# DriverPrototype.net
KiCad netlist of a schematic drawn in Altium Designer
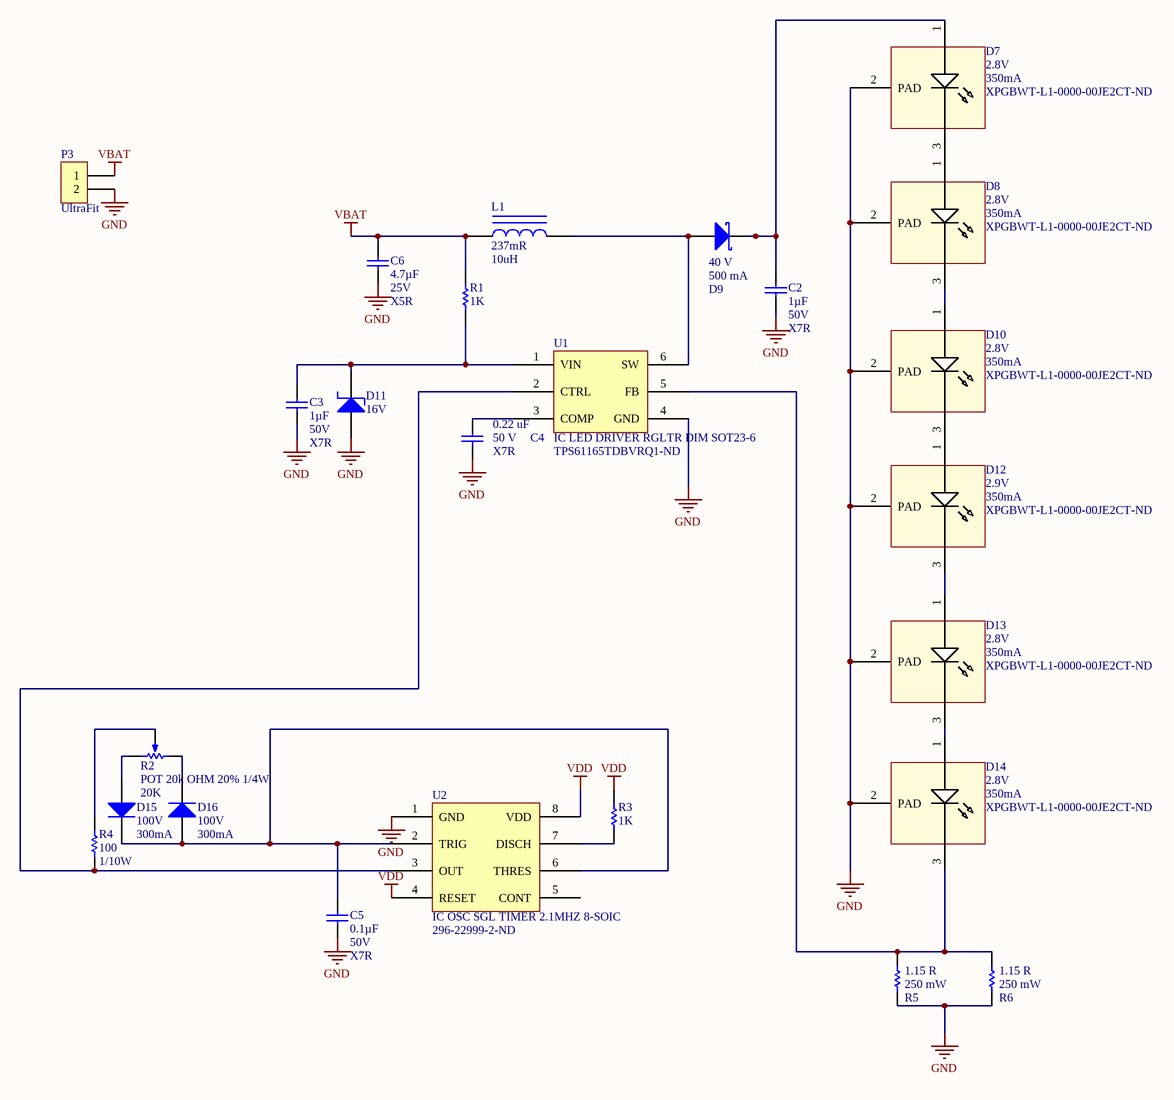
[diagram p0: DriverPrototype.SchDoc]

(export (version "E")
  (design (tool "Eeschema 10.0.6"))
  (components
    (comp (ref "C2")
      (value "CAP CER 1UF 50V 10% X7R 0603")
      (footprint "CAP, 0603")
      (description "1µF ±10% 50V Ceramic Capacitor X7R 0603 (1608 Metric)")
      (fields
        (field (name "TOLERANCE") "±10%")
        (field (name "CAPACITANCE") "1µF")
        (field (name "VOLTAGE") "50V")
        (field (name "TEMPERATURE COEFFICIENT") "X7R")
      )
      (libsource (lib "Schematic Diagrams") (part "CAP CER 1UF 50V 10% X7R 0603"))
    )
    (comp (ref "C3")
      (value "CAP CER 1UF 50V 10% X7R 0603")
      (footprint "CAP, 0603")
      (description "1µF ±10% 50V Ceramic Capacitor X7R 0603 (1608 Metric)")
      (fields
        (field (name "TOLERANCE") "±10%")
        (field (name "CAPACITANCE") "1µF")
        (field (name "VOLTAGE") "50V")
        (field (name "TEMPERATURE COEFFICIENT") "X7R")
      )
      (libsource (lib "Schematic Diagrams") (part "CAP CER 1UF 50V 10% X7R 0603"))
    )
    (comp (ref "C4")
      (value "CAP CER 0.22UF 50V X7R 0805")
      (footprint "CAP, 0805")
      (fields
        (field (name "MANUFACTURER") "Samsung")
        (field (name "MANUFACTURER PART NUMBER") "CL21B224KBFNNNE")
        (field (name "TOLERANCE") "10%")
      )
      (libsource (lib "Schematic Diagrams") (part "CAP CER 0.22UF 50V X7R 0805"))
    )
    (comp (ref "C5")
      (value "CAP CER 0.1UF 50V 10% X7R 0603")
      (footprint "CAP, 0603")
      (description "0.10µF ±10% 50V Ceramic Capacitor X7R 0603 (1608 Metric)")
      (fields
        (field (name "TOLERANCE") "±10%")
        (field (name "CAPACITANCE") "0.1µF")
        (field (name "VOLTAGE") "50V")
        (field (name "TEMPERATURE COEFFICIENT") "X7R")
      )
      (libsource (lib "Schematic Diagrams") (part "CAP CER 0.1UF 50V 10% X7R 0603"))
    )
    (comp (ref "C6")
      (value "CAP CER 4700PF 400VAC Y5V RADIAL")
      (footprint "CAP 4700PF 400VAC Y5V RADIAL")
      (description "4.7µF ±10% 25V Ceramic Capacitor X5R 0603 (1608 Metric)")
      (fields
        (field (name "TOLERANCE") "±10%")
        (field (name "CAPACITANCE") "4.7µF")
        (field (name "VOLTAGE") "25V")
        (field (name "TEMPERATURE COEFFICIENT") "X5R")
      )
      (libsource (lib "Schematic Diagrams") (part "CAP CER 4.7UF 25V 10% X5R 0603"))
    )
    (comp (ref "D7")
      (value "LED XLAMP COOL WHITE 5700K 2SMD")
      (footprint "LED CREE XP-E2 1414 2-SMD")
      (description "LED Lighting XLamp® XP-E2 White, Cool 5700K 2.9V 350mA 110° 1414 (3535 Metric)")
      (fields
        (field (name "MANUFACTURER") "Cree")
        (field (name "MANUFACTURER PART NUMBER") "XPGBWT-L1-0000-00JE2")
        (field (name "FORWARD VOLTAGE") "2.8V")
        (field (name "TEST CURRENT") "350mA")
        (field (name "SUPPLIER PART NUMBER 1") "XPGBWT-L1-0000-00JE2CT-ND")
      )
      (libsource (lib "Schematic Diagrams") (part "LED XLAMP COOL WHITE 5700K 2SMD"))
    )
    (comp (ref "D8")
      (value "LED XLAMP COOL WHITE 5700K 2SMD")
      (footprint "LED CREE XP-E2 1414 2-SMD")
      (description "LED Lighting XLamp® XP-E2 White, Cool 5700K 2.9V 350mA 110° 1414 (3535 Metric)")
      (fields
        (field (name "MANUFACTURER") "Cree")
        (field (name "MANUFACTURER PART NUMBER") "XPGBWT-L1-0000-00JE2")
        (field (name "FORWARD VOLTAGE") "2.8V")
        (field (name "TEST CURRENT") "350mA")
        (field (name "SUPPLIER PART NUMBER 1") "XPGBWT-L1-0000-00JE2CT-ND")
      )
      (libsource (lib "Schematic Diagrams") (part "LED XLAMP COOL WHITE 5700K 2SMD"))
    )
    (comp (ref "D9")
      (value "DIODE SCHOTTKY 40V 500MA SOD123")
      (footprint "SOD123")
      (description "Diode Schottky 40V 500mA Surface Mount SOD-123")
      (fields
        (field (name "MANUFACTURER") "ON Semiconductor / Fairchild")
        (field (name "MANUFACTURER PART NUMBER") "MBR0540")
      )
      (libsource (lib "Schematic Diagrams") (part "DIODE SCHOTTKY 40V 500MA SOD123"))
    )
    (comp (ref "D10")
      (value "LED XLAMP COOL WHITE 5700K 2SMD")
      (footprint "LED CREE XP-E2 1414 2-SMD")
      (description "LED Lighting XLamp® XP-E2 White, Cool 5700K 2.9V 350mA 110° 1414 (3535 Metric)")
      (fields
        (field (name "MANUFACTURER") "Cree")
        (field (name "MANUFACTURER PART NUMBER") "XPGBWT-L1-0000-00JE2")
        (field (name "FORWARD VOLTAGE") "2.8V")
        (field (name "TEST CURRENT") "350mA")
        (field (name "SUPPLIER PART NUMBER 1") "XPGBWT-L1-0000-00JE2CT-ND")
      )
      (libsource (lib "Schematic Diagrams") (part "LED XLAMP COOL WHITE 5700K 2SMD"))
    )
    (comp (ref "D11")
      (value "DIODE ZENER 16V 5W DO-214AA (SMB)")
      (footprint "DO-214AA Diode")
      (description "Zener Diode 16V 5W ±5% Surface Mount DO-214AA (SMB)")
      (fields
        (field (name "MANUFACTURE PART NUMBER") "SMBJ5353B-TP")
        (field (name "VOLTAGE - ZENER (NOM)") "16V")
      )
      (libsource (lib "Schematic Diagrams") (part "DIODE ZENER 16V 5W DO-214AA (SMB)"))
    )
    (comp (ref "D12")
      (value "LED XLAMP COOL WHITE 5700K 2SMD")
      (footprint "LED CREE XP-E2 1414 2-SMD")
      (description "LED Lighting XLamp® XP-E2 White, Cool 5700K 2.9V 350mA 110° 1414 (3535 Metric)")
      (fields
        (field (name "MANUFACTURER") "Cree")
        (field (name "MANUFACTURER PART NUMBER") "XPGBWT-L1-0000-00JE2")
        (field (name "FORWARD VOLTAGE") "2.9V")
        (field (name "TEST CURRENT") "350mA")
        (field (name "SUPPLIER PART NUMBER 1") "XPGBWT-L1-0000-00JE2CT-ND")
      )
      (libsource (lib "Schematic Diagrams") (part "LED XLAMP COOL WHITE 5700K 2SMD"))
    )
    (comp (ref "D13")
      (value "LED XLAMP COOL WHITE 5700K 2SMD")
      (footprint "LED CREE XP-E2 1414 2-SMD")
      (description "LED Lighting XLamp® XP-E2 White, Cool 5700K 2.9V 350mA 110° 1414 (3535 Metric)")
      (fields
        (field (name "MANUFACTURER") "Cree")
        (field (name "MANUFACTURER PART NUMBER") "XPGBWT-L1-0000-00JE2")
        (field (name "FORWARD VOLTAGE") "2.8V")
        (field (name "TEST CURRENT") "350mA")
        (field (name "SUPPLIER PART NUMBER 1") "XPGBWT-L1-0000-00JE2CT-ND")
      )
      (libsource (lib "Schematic Diagrams") (part "LED XLAMP COOL WHITE 5700K 2SMD"))
    )
    (comp (ref "D14")
      (value "LED XLAMP COOL WHITE 5700K 2SMD")
      (footprint "LED CREE XP-E2 1414 2-SMD")
      (description "LED Lighting XLamp® XP-E2 White, Cool 5700K 2.9V 350mA 110° 1414 (3535 Metric)")
      (fields
        (field (name "MANUFACTURER") "Cree")
        (field (name "MANUFACTURER PART NUMBER") "XPGBWT-L1-0000-00JE2")
        (field (name "FORWARD VOLTAGE") "2.8V")
        (field (name "TEST CURRENT") "350mA")
        (field (name "SUPPLIER PART NUMBER 1") "XPGBWT-L1-0000-00JE2CT-ND")
      )
      (libsource (lib "Schematic Diagrams") (part "LED XLAMP COOL WHITE 5700K 2SMD"))
    )
    (comp (ref "D15")
      (value "DIODE GEN PURP 100V 300MA SOD123")
      (footprint "DIODE GEN PURP 100V 300MA SOD123")
      (description "Diode Standard 100V 300mA (DC) Surface Mount SOD-123")
      (fields
        (field (name "MANUFACTURER") "Diodes Zetex")
        (field (name "MANUFACTURER PART NUMBER") "1N4148WQ-7-F")
        (field (name "MAX REPETITIVE REVERSE VOLTAGE (VRRM)") "100V")
        (field (name "FORWARD CURRENT") "300mA")
      )
      (libsource (lib "Schematic Diagrams") (part "DIODE GEN PURP 100V 300MA SOD123"))
    )
    (comp (ref "D16")
      (value "DIODE GEN PURP 100V 300MA SOD123")
      (footprint "DIODE GEN PURP 100V 300MA SOD123")
      (description "Diode Standard 100V 300mA (DC) Surface Mount SOD-123")
      (fields
        (field (name "MANUFACTURER") "Diodes Zetex")
        (field (name "MANUFACTURER PART NUMBER") "1N4148WQ-7-F")
        (field (name "MAX REPETITIVE REVERSE VOLTAGE (VRRM)") "100V")
        (field (name "FORWARD CURRENT") "300mA")
      )
      (libsource (lib "Schematic Diagrams") (part "DIODE GEN PURP 100V 300MA SOD123"))
    )
    (comp (ref "L1")
      (value "FIXED IND 10UH 1.13A 237 MOHM")
      (footprint "INDP5050X20N")
      (description "10µH Shielded Wirewound Inductor 1.13A 237mOhm Max Nonstandard")
      (fields
        (field (name "MANUFACTURER") "TDK")
        (field (name "MANUFACTURER PART NUMBER") "VLCF5020T-100M1R1-1")
        (field (name "DC RESISTANCE (DCR)") "237mR")
        (field (name "INDUCTANCE") "10uH")
      )
      (libsource (lib "Schematic Diagrams") (part "FIXED IND 10UH 1.13A 237 MOHM"))
    )
    (comp (ref "P3")
      (value "CONN 2POS ULTRA-FIT 0.138\"")
      (footprint "CONN, 2POS ULTRA-FIT")
      (description "Connector Header Through Hole 2 position 0.138\" (3.50mm)")
      (fields
        (field (name "MANUFACTURER") "Molex")
        (field (name "MANUFACTURER PART NUMBER") "1722871102")
        (field (name "SERIES") "UltraFit")
      )
      (libsource (lib "Schematic Diagrams") (part "CONN 2POS ULTRA-FIT 0.138{dblquote}"))
    )
    (comp (ref "R1")
      (value "1K")
      (footprint "RES, 0603")
      (description "1k Ohm ±5% 0.1W, 1/10W Chip Resistor 0603 (1608 Metric)")
      (fields
        (field (name "MANUFACTURER") "Yageo")
        (field (name "MANUFACTURER PART NUMBER") "RC0603JR-071KL")
      )
      (libsource (lib "Schematic Diagrams") (part "RES 1K OHM 5% 1/10W 0603"))
    )
    (comp (ref "R2")
      (value "POT 20k OHM 20% 1/4W")
      (footprint "20K POT")
      (description "20k Ohm 0.25W, 1/4W Gull Wing Surface Mount Trimmer Potentiometer")
      (fields
        (field (name "POWER") "1/4W")
        (field (name "MANUFACTURE PART NUMBER") "23BR20KLFTR")
        (field (name "ALTIUM_VALUE") "20K")
      )
      (libsource (lib "Schematic Diagrams") (part "POT 20k OHM 20% 1/4W"))
    )
    (comp (ref "R3")
      (value "1K")
      (footprint "RES, 0603")
      (description "1k Ohm ±5% 0.1W, 1/10W Chip Resistor 0603 (1608 Metric)")
      (fields
        (field (name "MANUFACTURER") "Yageo")
        (field (name "MANUFACTURER PART NUMBER") "RC0603JR-071KL")
      )
      (libsource (lib "Schematic Diagrams") (part "RES 1K OHM 5% 1/10W 0603"))
    )
    (comp (ref "R4")
      (value "RES 100 OHM 1% 1/10W 0603")
      (footprint "RES, 0603")
      (description "100 Ohm ±1% 0.1W, 1/10W Chip Resistor 0603 (1608 Metric) Moisture Resistant Thick Film")
      (fields
        (field (name "TOLERANCE") "±1%")
        (field (name "RESISTANCE") "100")
        (field (name "POWER") "1/10W")
      )
      (libsource (lib "Schematic Diagrams") (part "RES 100 OHM 1% 1/10W 0603"))
    )
    (comp (ref "R5")
      (value "RES SMD 1.15 OHM 1% 1/4W 1206")
      (footprint "RES 1206")
      (fields
        (field (name "MANUFACTURER") "Yageo")
        (field (name "MANUFACTURER PART NUMBER") "RC1206FR-071R15L")
        (field (name "TOLERANCE") "1%")
      )
      (libsource (lib "Schematic Diagrams") (part "RES SMD 1.15 OHM 1% 1/4W 1206"))
    )
    (comp (ref "R6")
      (value "RES SMD 1.15 OHM 1% 1/4W 1206")
      (footprint "RES 1206")
      (fields
        (field (name "MANUFACTURER") "Yageo")
        (field (name "MANUFACTURER PART NUMBER") "RC1206FR-071R15L")
        (field (name "TOLERANCE") "1%")
      )
      (libsource (lib "Schematic Diagrams") (part "RES SMD 1.15 OHM 1% 1/4W 1206"))
    )
    (comp (ref "U1")
      (value "IC LED DRIVER RGLTR DIM SOT23-6")
      (footprint "SOT23-6_N")
      (description "LED Driver IC 1 Output DC DC Regulator Step-Up (Boost) PWM Dimming 1.2A (Switch) SOT-23-6")
      (fields
        (field (name "MANUFACTURER") "Texas Instruments")
        (field (name "MANUFACTURER PART NUMBER") "TPS61165TDBVRQ1")
        (field (name "SUPPLIER PART NUMBER 1") "TPS61165TDBVRQ1-ND")
      )
      (libsource (lib "Schematic Diagrams") (part "IC LED DRIVER RGLTR DIM SOT23-6"))
    )
    (comp (ref "U2")
      (value "IC OSC SGL TIMER 2.1MHZ 8-SOIC")
      (footprint "SOIC8")
      (description "555 Type, Timer/Oscillator (Single) IC 2.1MHz 8-SOIC")
      (fields
        (field (name "MANUFACTURER") "Texas Instruments")
        (field (name "MANUFACTURER PART NUMBER") "TLC555QDRQ1")
        (field (name "SUPPLIER PART NUMBER 1") "296-22999-2-ND")
      )
      (libsource (lib "Schematic Diagrams") (part "IC OSC SGL TIMER 2.1MHZ 8-SOIC"))
    )
  )
  (nets
    (net (code "1") (name "GND") (class "Default")
      (node (ref "C2") (pin "2") (pinfunction "2_2") (pintype "passive"))
      (node (ref "C3") (pin "2") (pinfunction "2_2") (pintype "passive"))
      (node (ref "C4") (pin "2") (pinfunction "2_2") (pintype "passive"))
      (node (ref "C5") (pin "1") (pinfunction "1_1") (pintype "passive"))
      (node (ref "C6") (pin "2") (pinfunction "2_2") (pintype "passive"))
      (node (ref "D10") (pin "2") (pinfunction "PAD_2") (pintype "passive"))
      (node (ref "D11") (pin "1") (pinfunction "A_1") (pintype "passive"))
      (node (ref "D12") (pin "2") (pinfunction "PAD_2") (pintype "passive"))
      (node (ref "D13") (pin "2") (pinfunction "PAD_2") (pintype "passive"))
      (node (ref "D14") (pin "2") (pinfunction "PAD_2") (pintype "passive"))
      (node (ref "D7") (pin "2") (pinfunction "PAD_2") (pintype "passive"))
      (node (ref "D8") (pin "2") (pinfunction "PAD_2") (pintype "passive"))
      (node (ref "P3") (pin "2") (pinfunction "2_2") (pintype "passive"))
      (node (ref "R5") (pin "2") (pinfunction "2_2") (pintype "passive"))
      (node (ref "R6") (pin "2") (pinfunction "2_2") (pintype "passive"))
      (node (ref "U1") (pin "4") (pinfunction "GND_4") (pintype "passive"))
      (node (ref "U2") (pin "1") (pinfunction "GND_1") (pintype "passive"))
    )
    (net (code "2") (name "Net-(D7-A)") (class "Default")
      (node (ref "C2") (pin "1") (pinfunction "1_1") (pintype "passive"))
      (node (ref "D7") (pin "1") (pinfunction "A_1") (pintype "passive"))
      (node (ref "D9") (pin "2") (pinfunction "K_2") (pintype "passive"))
    )
    (net (code "3") (name "Net-(D7-K)") (class "Default")
      (node (ref "D7") (pin "3") (pinfunction "K_3") (pintype "passive"))
      (node (ref "D8") (pin "1") (pinfunction "A_1") (pintype "passive"))
    )
    (net (code "4") (name "Net-(D9-A)") (class "Default")
      (node (ref "D9") (pin "1") (pinfunction "A_1") (pintype "passive"))
      (node (ref "L1") (pin "2") (pinfunction "2_2") (pintype "passive"))
      (node (ref "U1") (pin "6") (pinfunction "SW_6") (pintype "passive"))
    )
    (net (code "5") (name "Net-(D10-A)") (class "Default")
      (node (ref "D10") (pin "1") (pinfunction "A_1") (pintype "passive"))
      (node (ref "D8") (pin "3") (pinfunction "K_3") (pintype "passive"))
    )
    (net (code "6") (name "Net-(D10-K)") (class "Default")
      (node (ref "D10") (pin "3") (pinfunction "K_3") (pintype "passive"))
      (node (ref "D12") (pin "1") (pinfunction "A_1") (pintype "passive"))
    )
    (net (code "7") (name "Net-(D11-K)") (class "Default")
      (node (ref "C3") (pin "1") (pinfunction "1_1") (pintype "passive"))
      (node (ref "D11") (pin "2") (pinfunction "K_2") (pintype "passive"))
      (node (ref "R1") (pin "2") (pinfunction "2_2") (pintype "passive"))
      (node (ref "U1") (pin "1") (pinfunction "VIN_1") (pintype "passive"))
    )
    (net (code "8") (name "Net-(D12-K)") (class "Default")
      (node (ref "D12") (pin "3") (pinfunction "K_3") (pintype "passive"))
      (node (ref "D13") (pin "1") (pinfunction "A_1") (pintype "passive"))
    )
    (net (code "9") (name "Net-(D13-K)") (class "Default")
      (node (ref "D13") (pin "3") (pinfunction "K_3") (pintype "passive"))
      (node (ref "D14") (pin "1") (pinfunction "A_1") (pintype "passive"))
    )
    (net (code "10") (name "Net-(D14-K)") (class "Default")
      (node (ref "D14") (pin "3") (pinfunction "K_3") (pintype "passive"))
      (node (ref "R5") (pin "1") (pinfunction "1_1") (pintype "passive"))
      (node (ref "R6") (pin "1") (pinfunction "1_1") (pintype "passive"))
      (node (ref "U1") (pin "5") (pinfunction "FB_5") (pintype "passive"))
    )
    (net (code "11") (name "Net-(D15-A)") (class "Default")
      (node (ref "D15") (pin "1") (pinfunction "A_1") (pintype "passive"))
      (node (ref "R2") (pin "3") (pinfunction "BOT_3") (pintype "passive"))
    )
    (net (code "12") (name "Net-(D15-K)") (class "Default")
      (node (ref "C5") (pin "2") (pinfunction "2_2") (pintype "passive"))
      (node (ref "D15") (pin "2") (pinfunction "K_2") (pintype "passive"))
      (node (ref "D16") (pin "1") (pinfunction "A_1") (pintype "passive"))
      (node (ref "U2") (pin "2") (pinfunction "TRIG_2") (pintype "passive"))
      (node (ref "U2") (pin "6") (pinfunction "THRES_6") (pintype "passive"))
    )
    (net (code "13") (name "Net-(D16-K)") (class "Default")
      (node (ref "D16") (pin "2") (pinfunction "K_2") (pintype "passive"))
      (node (ref "R2") (pin "1") (pinfunction "TOP_1") (pintype "passive"))
    )
    (net (code "14") (name "Net-(R2-TAP)") (class "Default")
      (node (ref "R2") (pin "2") (pinfunction "TAP_2") (pintype "passive"))
      (node (ref "R4") (pin "1") (pinfunction "1_1") (pintype "passive"))
    )
    (net (code "15") (name "Net-(U1-COMP)") (class "Default")
      (node (ref "C4") (pin "1") (pinfunction "1_1") (pintype "passive"))
      (node (ref "U1") (pin "3") (pinfunction "COMP_3") (pintype "passive"))
    )
    (net (code "16") (name "Net-(U1-CTRL)") (class "Default")
      (node (ref "R4") (pin "2") (pinfunction "2_2") (pintype "passive"))
      (node (ref "U1") (pin "2") (pinfunction "CTRL_2") (pintype "passive"))
      (node (ref "U2") (pin "3") (pinfunction "OUT_3") (pintype "passive"))
    )
    (net (code "17") (name "Net-(U2-DISCH)") (class "Default")
      (node (ref "R3") (pin "2") (pinfunction "2_2") (pintype "passive"))
      (node (ref "U2") (pin "7") (pinfunction "DISCH_7") (pintype "passive"))
    )
    (net (code "18") (name "VBAT") (class "Default")
      (node (ref "C6") (pin "1") (pinfunction "1_1") (pintype "passive"))
      (node (ref "L1") (pin "1") (pinfunction "1_1") (pintype "passive"))
      (node (ref "P3") (pin "1") (pinfunction "1_1") (pintype "passive"))
      (node (ref "R1") (pin "1") (pinfunction "1_1") (pintype "passive"))
    )
    (net (code "19") (name "VDD") (class "Default")
      (node (ref "R3") (pin "1") (pinfunction "1_1") (pintype "passive"))
      (node (ref "U2") (pin "4") (pinfunction "RESET_4") (pintype "passive"))
      (node (ref "U2") (pin "8") (pinfunction "VDD_8") (pintype "passive"))
    )
    (net (code "20") (name "unconnected-(U2-CONT-Pad5)") (class "Default")
      (node (ref "U2") (pin "5") (pinfunction "CONT_5") (pintype "passive"))
    )
  )
)
